# PCIE_Connector.net
KiCad netlist of a schematic drawn in Altium Designer
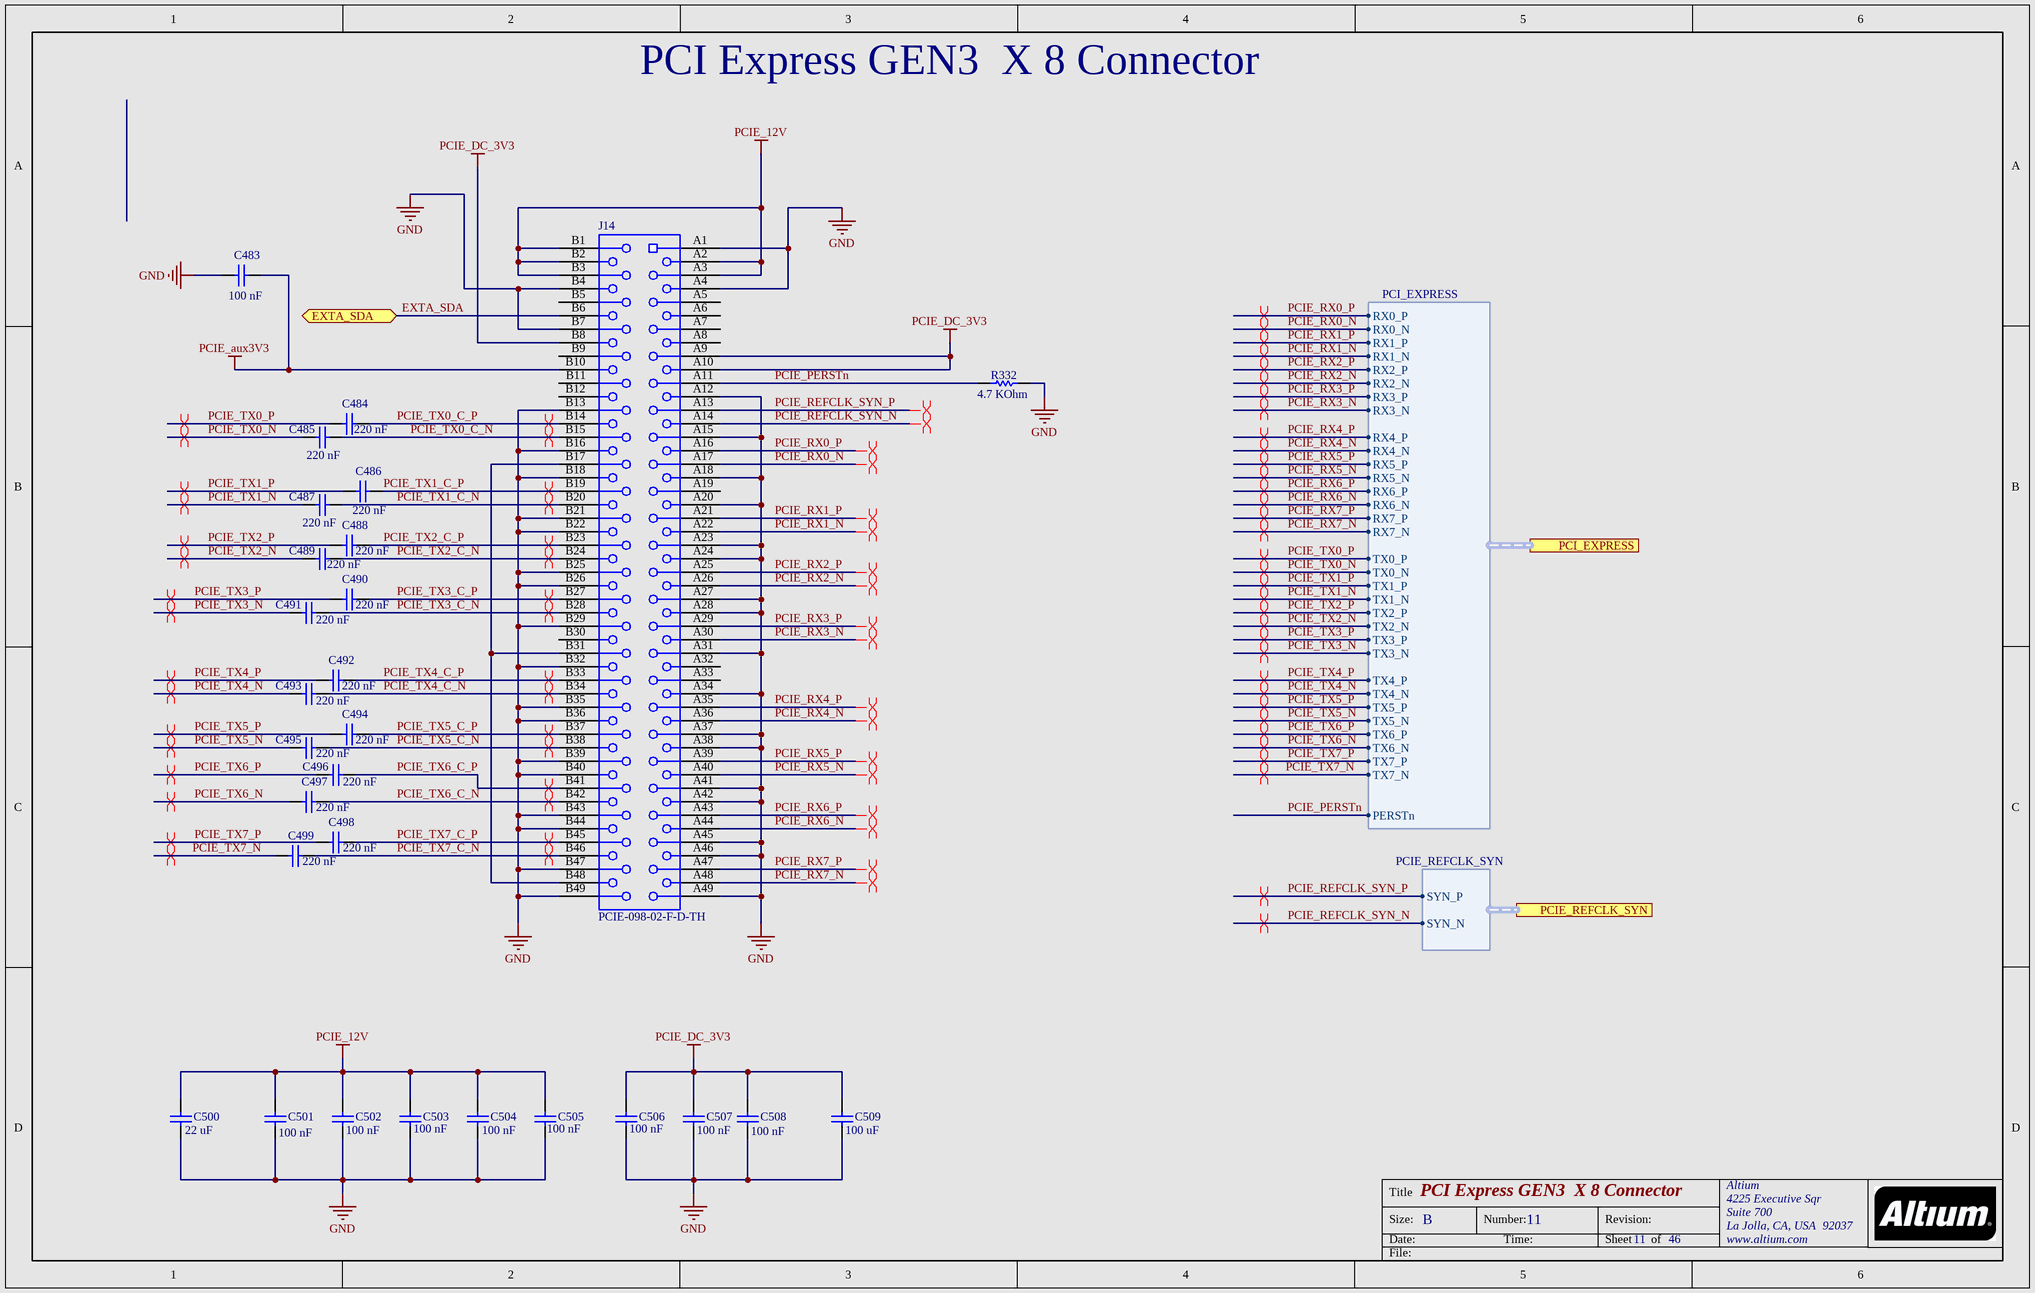
[diagram p0: PCIE_Connector.SchDoc]

(export (version "E")
  (design (tool "Eeschema 10.0.6"))
  (components
    (comp (ref "C483")
      (value "C1005X7R1E104M")
      (footprint "CAPC1005X55X10LL05")
      (description "Chip Capacitor, 0.1 uF, +/- 20%, 25 V, -55 to 125 degC, 0402 (1005 Metric), RoHS, Tape and Reel")
      (fields (field (name "TOLERANCE") "20%") (field (name "CAPACITANCE") "100 nF"))
      (libsource (lib "Altium Content Vault") (part "CAP-NP-2"))
    )
    (comp (ref "C484")
      (value "GRM155R61A224KE19D")
      (footprint "CAPC1005X55X25NL05T10")
      (description "Chip Capacitor, 220 nF, +/- 10%, 10 V, -55 to 85 degC, 0402 (1005 Metric), RoHS, Tape and Reel")
      (fields
        (field (name "TOLERANCE") "10%")
        (field (name "CAPACITANCE") "220 nF")
        (field (name "MANUFACTURER") "Basic Passives")
      )
      (libsource (lib "Altium Content Vault") (part "CAP-NP-2"))
    )
    (comp (ref "C485")
      (value "GRM155R61A224KE19D")
      (footprint "CAPC1005X55X25NL05T10")
      (description "Chip Capacitor, 220 nF, +/- 10%, 10 V, -55 to 85 degC, 0402 (1005 Metric), RoHS, Tape and Reel")
      (fields
        (field (name "TOLERANCE") "10%")
        (field (name "CAPACITANCE") "220 nF")
        (field (name "MANUFACTURER") "Basic Passives")
      )
      (libsource (lib "Altium Content Vault") (part "CAP-NP-2"))
    )
    (comp (ref "C486")
      (value "GRM155R61A224KE19D")
      (footprint "CAPC1005X55X25NL05T10")
      (description "Chip Capacitor, 220 nF, +/- 10%, 10 V, -55 to 85 degC, 0402 (1005 Metric), RoHS, Tape and Reel")
      (fields
        (field (name "TOLERANCE") "10%")
        (field (name "CAPACITANCE") "220 nF")
        (field (name "MANUFACTURER") "Basic Passives")
      )
      (libsource (lib "Altium Content Vault") (part "CAP-NP-2"))
    )
    (comp (ref "C487")
      (value "GRM155R61A224KE19D")
      (footprint "CAPC1005X55X25NL05T10")
      (description "Chip Capacitor, 220 nF, +/- 10%, 10 V, -55 to 85 degC, 0402 (1005 Metric), RoHS, Tape and Reel")
      (fields
        (field (name "TOLERANCE") "10%")
        (field (name "CAPACITANCE") "220 nF")
        (field (name "MANUFACTURER") "Basic Passives")
      )
      (libsource (lib "Altium Content Vault") (part "CAP-NP-2"))
    )
    (comp (ref "C488")
      (value "GRM155R61A224KE19D")
      (footprint "CAPC1005X55X25NL05T10")
      (description "Chip Capacitor, 220 nF, +/- 10%, 10 V, -55 to 85 degC, 0402 (1005 Metric), RoHS, Tape and Reel")
      (fields
        (field (name "TOLERANCE") "10%")
        (field (name "CAPACITANCE") "220 nF")
        (field (name "MANUFACTURER") "Basic Passives")
      )
      (libsource (lib "Altium Content Vault") (part "CAP-NP-2"))
    )
    (comp (ref "C489")
      (value "GRM155R61A224KE19D")
      (footprint "CAPC1005X55X25NL05T10")
      (description "Chip Capacitor, 220 nF, +/- 10%, 10 V, -55 to 85 degC, 0402 (1005 Metric), RoHS, Tape and Reel")
      (fields
        (field (name "TOLERANCE") "10%")
        (field (name "CAPACITANCE") "220 nF")
        (field (name "MANUFACTURER") "Basic Passives")
      )
      (libsource (lib "Altium Content Vault") (part "CAP-NP-2"))
    )
    (comp (ref "C490")
      (value "GRM155R61A224KE19D")
      (footprint "CAPC1005X55X25NL05T10")
      (description "Chip Capacitor, 220 nF, +/- 10%, 10 V, -55 to 85 degC, 0402 (1005 Metric), RoHS, Tape and Reel")
      (fields
        (field (name "TOLERANCE") "10%")
        (field (name "CAPACITANCE") "220 nF")
        (field (name "MANUFACTURER") "Basic Passives")
      )
      (libsource (lib "Altium Content Vault") (part "CAP-NP-2"))
    )
    (comp (ref "C491")
      (value "GRM155R61A224KE19D")
      (footprint "CAPC1005X55X25NL05T10")
      (description "Chip Capacitor, 220 nF, +/- 10%, 10 V, -55 to 85 degC, 0402 (1005 Metric), RoHS, Tape and Reel")
      (fields
        (field (name "TOLERANCE") "10%")
        (field (name "CAPACITANCE") "220 nF")
        (field (name "MANUFACTURER") "Basic Passives")
      )
      (libsource (lib "Altium Content Vault") (part "CAP-NP-2"))
    )
    (comp (ref "C492")
      (value "GRM155R61A224KE19D")
      (footprint "CAPC1005X55X25NL05T10")
      (description "Chip Capacitor, 220 nF, +/- 10%, 10 V, -55 to 85 degC, 0402 (1005 Metric), RoHS, Tape and Reel")
      (fields
        (field (name "TOLERANCE") "10%")
        (field (name "CAPACITANCE") "220 nF")
        (field (name "MANUFACTURER") "Basic Passives")
      )
      (libsource (lib "Altium Content Vault") (part "CAP-NP-2"))
    )
    (comp (ref "C493")
      (value "GRM155R61A224KE19D")
      (footprint "CAPC1005X55X25NL05T10")
      (description "Chip Capacitor, 220 nF, +/- 10%, 10 V, -55 to 85 degC, 0402 (1005 Metric), RoHS, Tape and Reel")
      (fields
        (field (name "TOLERANCE") "10%")
        (field (name "CAPACITANCE") "220 nF")
        (field (name "MANUFACTURER") "Basic Passives")
      )
      (libsource (lib "Altium Content Vault") (part "CAP-NP-2"))
    )
    (comp (ref "C494")
      (value "GRM155R61A224KE19D")
      (footprint "CAPC1005X55X25NL05T10")
      (description "Chip Capacitor, 220 nF, +/- 10%, 10 V, -55 to 85 degC, 0402 (1005 Metric), RoHS, Tape and Reel")
      (fields
        (field (name "TOLERANCE") "10%")
        (field (name "CAPACITANCE") "220 nF")
        (field (name "MANUFACTURER") "Basic Passives")
      )
      (libsource (lib "Altium Content Vault") (part "CAP-NP-2"))
    )
    (comp (ref "C495")
      (value "GRM155R61A224KE19D")
      (footprint "CAPC1005X55X25NL05T10")
      (description "Chip Capacitor, 220 nF, +/- 10%, 10 V, -55 to 85 degC, 0402 (1005 Metric), RoHS, Tape and Reel")
      (fields
        (field (name "TOLERANCE") "10%")
        (field (name "CAPACITANCE") "220 nF")
        (field (name "MANUFACTURER") "Basic Passives")
      )
      (libsource (lib "Altium Content Vault") (part "CAP-NP-2"))
    )
    (comp (ref "C496")
      (value "GRM155R61A224KE19D")
      (footprint "CAPC1005X55X25NL05T10")
      (description "Chip Capacitor, 220 nF, +/- 10%, 10 V, -55 to 85 degC, 0402 (1005 Metric), RoHS, Tape and Reel")
      (fields
        (field (name "TOLERANCE") "10%")
        (field (name "CAPACITANCE") "220 nF")
        (field (name "MANUFACTURER") "Basic Passives")
      )
      (libsource (lib "Altium Content Vault") (part "CAP-NP-2"))
    )
    (comp (ref "C497")
      (value "GRM155R61A224KE19D")
      (footprint "CAPC1005X55X25NL05T10")
      (description "Chip Capacitor, 220 nF, +/- 10%, 10 V, -55 to 85 degC, 0402 (1005 Metric), RoHS, Tape and Reel")
      (fields
        (field (name "TOLERANCE") "10%")
        (field (name "CAPACITANCE") "220 nF")
        (field (name "MANUFACTURER") "Basic Passives")
      )
      (libsource (lib "Altium Content Vault") (part "CAP-NP-2"))
    )
    (comp (ref "C498")
      (value "GRM155R61A224KE19D")
      (footprint "CAPC1005X55X25NL05T10")
      (description "Chip Capacitor, 220 nF, +/- 10%, 10 V, -55 to 85 degC, 0402 (1005 Metric), RoHS, Tape and Reel")
      (fields
        (field (name "TOLERANCE") "10%")
        (field (name "CAPACITANCE") "220 nF")
        (field (name "MANUFACTURER") "Basic Passives")
      )
      (libsource (lib "Altium Content Vault") (part "CAP-NP-2"))
    )
    (comp (ref "C499")
      (value "GRM155R61A224KE19D")
      (footprint "CAPC1005X55X25NL05T10")
      (description "Chip Capacitor, 220 nF, +/- 10%, 10 V, -55 to 85 degC, 0402 (1005 Metric), RoHS, Tape and Reel")
      (fields
        (field (name "TOLERANCE") "10%")
        (field (name "CAPACITANCE") "220 nF")
        (field (name "MANUFACTURER") "Basic Passives")
      )
      (libsource (lib "Altium Content Vault") (part "CAP-NP-2"))
    )
    (comp (ref "C500")
      (value "GRM31CR61E226KE15L")
      (footprint "CAPC3216X180X55ML20T25")
      (description "Chip Capacitor, 22 uF, +/- 10%, 25 V, -55 to 85 degC, 1206 (3216 Metric), RoHS, Tape and Reel")
      (fields (field (name "TOLERANCE") "10%") (field (name "CAPACITANCE") "22 uF"))
      (libsource (lib "Altium Content Vault") (part "CAP-NP-2"))
    )
    (comp (ref "C501")
      (value "C1005X7R1E104M")
      (footprint "CAPC1005X55X10LL05")
      (description "Chip Capacitor, 0.1 uF, +/- 20%, 25 V, -55 to 125 degC, 0402 (1005 Metric), RoHS, Tape and Reel")
      (fields (field (name "TOLERANCE") "20%") (field (name "CAPACITANCE") "100 nF"))
      (libsource (lib "Altium Content Vault") (part "CAP-NP-2"))
    )
    (comp (ref "C502")
      (value "C1005X7R1E104M")
      (footprint "CAPC1005X55X10LL05")
      (description "Chip Capacitor, 0.1 uF, +/- 20%, 25 V, -55 to 125 degC, 0402 (1005 Metric), RoHS, Tape and Reel")
      (fields (field (name "TOLERANCE") "20%") (field (name "CAPACITANCE") "100 nF"))
      (libsource (lib "Altium Content Vault") (part "CAP-NP-2"))
    )
    (comp (ref "C503")
      (value "C1005X7R1E104M")
      (footprint "CAPC1005X55X10LL05")
      (description "Chip Capacitor, 0.1 uF, +/- 20%, 25 V, -55 to 125 degC, 0402 (1005 Metric), RoHS, Tape and Reel")
      (fields (field (name "TOLERANCE") "20%") (field (name "CAPACITANCE") "100 nF"))
      (libsource (lib "Altium Content Vault") (part "CAP-NP-2"))
    )
    (comp (ref "C504")
      (value "C1005X7R1E104M")
      (footprint "CAPC1005X55X10LL05")
      (description "Chip Capacitor, 0.1 uF, +/- 20%, 25 V, -55 to 125 degC, 0402 (1005 Metric), RoHS, Tape and Reel")
      (fields (field (name "TOLERANCE") "20%") (field (name "CAPACITANCE") "100 nF"))
      (libsource (lib "Altium Content Vault") (part "CAP-NP-2"))
    )
    (comp (ref "C505")
      (value "C1005X7R1E104M")
      (footprint "CAPC1005X55X10LL05")
      (description "Chip Capacitor, 0.1 uF, +/- 20%, 25 V, -55 to 125 degC, 0402 (1005 Metric), RoHS, Tape and Reel")
      (fields (field (name "TOLERANCE") "20%") (field (name "CAPACITANCE") "100 nF"))
      (libsource (lib "Altium Content Vault") (part "CAP-NP-2"))
    )
    (comp (ref "C506")
      (value "C1005X7R1E104M")
      (footprint "CAPC1005X55X10LL05")
      (description "Chip Capacitor, 0.1 uF, +/- 20%, 25 V, -55 to 125 degC, 0402 (1005 Metric), RoHS, Tape and Reel")
      (fields (field (name "TOLERANCE") "20%") (field (name "CAPACITANCE") "100 nF"))
      (libsource (lib "Altium Content Vault") (part "CAP-NP-2"))
    )
    (comp (ref "C507")
      (value "C1005X7R1E104M")
      (footprint "CAPC1005X55X10LL05")
      (description "Chip Capacitor, 0.1 uF, +/- 20%, 25 V, -55 to 125 degC, 0402 (1005 Metric), RoHS, Tape and Reel")
      (fields (field (name "TOLERANCE") "20%") (field (name "CAPACITANCE") "100 nF"))
      (libsource (lib "Altium Content Vault") (part "CAP-NP-2"))
    )
    (comp (ref "C508")
      (value "C1005X7R1E104M")
      (footprint "CAPC1005X55X10LL05")
      (description "Chip Capacitor, 0.1 uF, +/- 20%, 25 V, -55 to 125 degC, 0402 (1005 Metric), RoHS, Tape and Reel")
      (fields (field (name "TOLERANCE") "20%") (field (name "CAPACITANCE") "100 nF"))
      (libsource (lib "Altium Content Vault") (part "CAP-NP-2"))
    )
    (comp (ref "C509")
      (value "GRM31CR60J107ME39L")
      (footprint "CAPC3216X190X55ML30T25")
      (description "Chip Capacitor, 100 uF, +/- 20%, 6.3 V, -55 to 85 degC, 1206 (3216 Metric), RoHS, Tape and Reel")
      (fields (field (name "TOLERANCE") "20%") (field (name "CAPACITANCE") "100 uF"))
      (libsource (lib "Altium Content Vault") (part "CAP-NP-2"))
    )
    (comp (ref "J14")
      (value "PCIE-098-02-F-D-TH")
      (footprint "SMTC-PCIE-098-02-F-D-TH_V")
      (fields (field (name "MANUFACTURER") "Samtec"))
      (libsource (lib "Altium Content Vault") (part "CMP-1707-00002-1"))
    )
    (comp (ref "R332")
      (value "ERJ-2RKF4701X")
      (footprint "RESC1005X40X25LL05T05")
      (description "Chip Resistor, 4.7 KOhm, +/- 1%, 0.1 W, -55 to 155 degC, 0402 (1005 Metric), RoHS, Tape and Reel")
      (fields (field (name "TOLERANCE") "1%") (field (name "RESISTANCE") "4.7 KOhm"))
      (libsource (lib "Altium Content Vault") (part "RES-2"))
    )
  )
  (nets
    (net (code "3") (name "/EXTA_SDA") (class "Default")
      (node (ref "J14") (pin "B6") (pinfunction "B6_B6") (pintype "passive"))
    )
    (net (code "4") (name "/PCIE_PERSTn") (class "Default")
      (node (ref "J14") (pin "A11") (pinfunction "A11_A11") (pintype "passive"))
      (node (ref "R332") (pin "1") (pinfunction "1_1") (pintype "passive"))
    )
    (net (code "5") (name "/PCIE_REFCLK_SYN_N") (class "Default")
      (node (ref "J14") (pin "A14") (pinfunction "A14_A14") (pintype "passive"))
    )
    (net (code "6") (name "/PCIE_REFCLK_SYN_P") (class "Default")
      (node (ref "J14") (pin "A13") (pinfunction "A13_A13") (pintype "passive"))
    )
    (net (code "7") (name "/PCIE_RX0_N") (class "Default")
      (node (ref "J14") (pin "A17") (pinfunction "A17_A17") (pintype "passive"))
    )
    (net (code "8") (name "/PCIE_RX0_P") (class "Default")
      (node (ref "J14") (pin "A16") (pinfunction "A16_A16") (pintype "passive"))
    )
    (net (code "9") (name "/PCIE_RX1_N") (class "Default")
      (node (ref "J14") (pin "A22") (pinfunction "A22_A22") (pintype "passive"))
    )
    (net (code "10") (name "/PCIE_RX1_P") (class "Default")
      (node (ref "J14") (pin "A21") (pinfunction "A21_A21") (pintype "passive"))
    )
    (net (code "11") (name "/PCIE_RX2_N") (class "Default")
      (node (ref "J14") (pin "A26") (pinfunction "A26_A26") (pintype "passive"))
    )
    (net (code "12") (name "/PCIE_RX2_P") (class "Default")
      (node (ref "J14") (pin "A25") (pinfunction "A25_A25") (pintype "passive"))
    )
    (net (code "13") (name "/PCIE_RX3_N") (class "Default")
      (node (ref "J14") (pin "A30") (pinfunction "A30_A30") (pintype "passive"))
    )
    (net (code "14") (name "/PCIE_RX3_P") (class "Default")
      (node (ref "J14") (pin "A29") (pinfunction "A29_A29") (pintype "passive"))
    )
    (net (code "15") (name "/PCIE_RX4_N") (class "Default")
      (node (ref "J14") (pin "A36") (pinfunction "A36_A36") (pintype "passive"))
    )
    (net (code "16") (name "/PCIE_RX4_P") (class "Default")
      (node (ref "J14") (pin "A35") (pinfunction "A35_A35") (pintype "passive"))
    )
    (net (code "17") (name "/PCIE_RX5_N") (class "Default")
      (node (ref "J14") (pin "A40") (pinfunction "A40_A40") (pintype "passive"))
    )
    (net (code "18") (name "/PCIE_RX5_P") (class "Default")
      (node (ref "J14") (pin "A39") (pinfunction "A39_A39") (pintype "passive"))
    )
    (net (code "19") (name "/PCIE_RX6_N") (class "Default")
      (node (ref "J14") (pin "A44") (pinfunction "A44_A44") (pintype "passive"))
    )
    (net (code "20") (name "/PCIE_RX6_P") (class "Default")
      (node (ref "J14") (pin "A43") (pinfunction "A43_A43") (pintype "passive"))
    )
    (net (code "21") (name "/PCIE_RX7_N") (class "Default")
      (node (ref "J14") (pin "A48") (pinfunction "A48_A48") (pintype "passive"))
    )
    (net (code "22") (name "/PCIE_RX7_P") (class "Default")
      (node (ref "J14") (pin "A47") (pinfunction "A47_A47") (pintype "passive"))
    )
    (net (code "23") (name "/PCIE_TX0_C_N") (class "Default")
      (node (ref "C485") (pin "2") (pinfunction "2_2") (pintype "passive"))
      (node (ref "J14") (pin "B15") (pinfunction "B15_B15") (pintype "passive"))
    )
    (net (code "24") (name "/PCIE_TX0_C_P") (class "Default")
      (node (ref "C484") (pin "2") (pinfunction "2_2") (pintype "passive"))
      (node (ref "J14") (pin "B14") (pinfunction "B14_B14") (pintype "passive"))
    )
    (net (code "25") (name "/PCIE_TX0_N") (class "Default")
      (node (ref "C485") (pin "1") (pinfunction "1_1") (pintype "passive"))
    )
    (net (code "26") (name "/PCIE_TX0_P") (class "Default")
      (node (ref "C484") (pin "1") (pinfunction "1_1") (pintype "passive"))
    )
    (net (code "27") (name "/PCIE_TX1_C_N") (class "Default")
      (node (ref "C487") (pin "2") (pinfunction "2_2") (pintype "passive"))
      (node (ref "J14") (pin "B20") (pinfunction "B20_B20") (pintype "passive"))
    )
    (net (code "28") (name "/PCIE_TX1_C_P") (class "Default")
      (node (ref "C486") (pin "2") (pinfunction "2_2") (pintype "passive"))
      (node (ref "J14") (pin "B19") (pinfunction "B19_B19") (pintype "passive"))
    )
    (net (code "29") (name "/PCIE_TX1_N") (class "Default")
      (node (ref "C487") (pin "1") (pinfunction "1_1") (pintype "passive"))
    )
    (net (code "30") (name "/PCIE_TX1_P") (class "Default")
      (node (ref "C486") (pin "1") (pinfunction "1_1") (pintype "passive"))
    )
    (net (code "31") (name "/PCIE_TX2_C_N") (class "Default")
      (node (ref "C489") (pin "2") (pinfunction "2_2") (pintype "passive"))
      (node (ref "J14") (pin "B24") (pinfunction "B24_B24") (pintype "passive"))
    )
    (net (code "32") (name "/PCIE_TX2_C_P") (class "Default")
      (node (ref "C488") (pin "2") (pinfunction "2_2") (pintype "passive"))
      (node (ref "J14") (pin "B23") (pinfunction "B23_B23") (pintype "passive"))
    )
    (net (code "33") (name "/PCIE_TX2_N") (class "Default")
      (node (ref "C489") (pin "1") (pinfunction "1_1") (pintype "passive"))
    )
    (net (code "34") (name "/PCIE_TX2_P") (class "Default")
      (node (ref "C488") (pin "1") (pinfunction "1_1") (pintype "passive"))
    )
    (net (code "35") (name "/PCIE_TX3_C_N") (class "Default")
      (node (ref "C491") (pin "2") (pinfunction "2_2") (pintype "passive"))
      (node (ref "J14") (pin "B28") (pinfunction "B28_B28") (pintype "passive"))
    )
    (net (code "36") (name "/PCIE_TX3_C_P") (class "Default")
      (node (ref "C490") (pin "2") (pinfunction "2_2") (pintype "passive"))
      (node (ref "J14") (pin "B27") (pinfunction "B27_B27") (pintype "passive"))
    )
    (net (code "37") (name "/PCIE_TX3_N") (class "Default")
      (node (ref "C491") (pin "1") (pinfunction "1_1") (pintype "passive"))
    )
    (net (code "38") (name "/PCIE_TX3_P") (class "Default")
      (node (ref "C490") (pin "1") (pinfunction "1_1") (pintype "passive"))
    )
    (net (code "39") (name "/PCIE_TX4_C_N") (class "Default")
      (node (ref "C493") (pin "2") (pinfunction "2_2") (pintype "passive"))
      (node (ref "J14") (pin "B34") (pinfunction "B34_B34") (pintype "passive"))
    )
    (net (code "40") (name "/PCIE_TX4_C_P") (class "Default")
      (node (ref "C492") (pin "2") (pinfunction "2_2") (pintype "passive"))
      (node (ref "J14") (pin "B33") (pinfunction "B33_B33") (pintype "passive"))
    )
    (net (code "41") (name "/PCIE_TX4_N") (class "Default")
      (node (ref "C493") (pin "1") (pinfunction "1_1") (pintype "passive"))
    )
    (net (code "42") (name "/PCIE_TX4_P") (class "Default")
      (node (ref "C492") (pin "1") (pinfunction "1_1") (pintype "passive"))
    )
    (net (code "43") (name "/PCIE_TX5_C_N") (class "Default")
      (node (ref "C495") (pin "2") (pinfunction "2_2") (pintype "passive"))
      (node (ref "J14") (pin "B38") (pinfunction "B38_B38") (pintype "passive"))
    )
    (net (code "44") (name "/PCIE_TX5_C_P") (class "Default")
      (node (ref "C494") (pin "2") (pinfunction "2_2") (pintype "passive"))
      (node (ref "J14") (pin "B37") (pinfunction "B37_B37") (pintype "passive"))
    )
    (net (code "45") (name "/PCIE_TX5_N") (class "Default")
      (node (ref "C495") (pin "1") (pinfunction "1_1") (pintype "passive"))
    )
    (net (code "46") (name "/PCIE_TX5_P") (class "Default")
      (node (ref "C494") (pin "1") (pinfunction "1_1") (pintype "passive"))
    )
    (net (code "47") (name "/PCIE_TX6_C_N") (class "Default")
      (node (ref "C497") (pin "2") (pinfunction "2_2") (pintype "passive"))
      (node (ref "J14") (pin "B42") (pinfunction "B42_B42") (pintype "passive"))
    )
    (net (code "48") (name "/PCIE_TX6_C_P") (class "Default")
      (node (ref "C496") (pin "2") (pinfunction "2_2") (pintype "passive"))
      (node (ref "J14") (pin "B41") (pinfunction "B41_B41") (pintype "passive"))
    )
    (net (code "49") (name "/PCIE_TX6_N") (class "Default")
      (node (ref "C497") (pin "1") (pinfunction "1_1") (pintype "passive"))
    )
    (net (code "50") (name "/PCIE_TX6_P") (class "Default")
      (node (ref "C496") (pin "1") (pinfunction "1_1") (pintype "passive"))
    )
    (net (code "51") (name "/PCIE_TX7_C_N") (class "Default")
      (node (ref "C499") (pin "2") (pinfunction "2_2") (pintype "passive"))
      (node (ref "J14") (pin "B46") (pinfunction "B46_B46") (pintype "passive"))
    )
    (net (code "52") (name "/PCIE_TX7_C_P") (class "Default")
      (node (ref "C498") (pin "2") (pinfunction "2_2") (pintype "passive"))
      (node (ref "J14") (pin "B45") (pinfunction "B45_B45") (pintype "passive"))
    )
    (net (code "53") (name "/PCIE_TX7_N") (class "Default")
      (node (ref "C499") (pin "1") (pinfunction "1_1") (pintype "passive"))
    )
    (net (code "54") (name "/PCIE_TX7_P") (class "Default")
      (node (ref "C498") (pin "1") (pinfunction "1_1") (pintype "passive"))
    )
    (net (code "57") (name "GND") (class "Default")
      (node (ref "C483") (pin "1") (pinfunction "1_1") (pintype "passive"))
      (node (ref "C500") (pin "1") (pinfunction "1_1") (pintype "passive"))
      (node (ref "C501") (pin "1") (pinfunction "1_1") (pintype "passive"))
      (node (ref "C502") (pin "1") (pinfunction "1_1") (pintype "passive"))
      (node (ref "C503") (pin "1") (pinfunction "1_1") (pintype "passive"))
      (node (ref "C504") (pin "1") (pinfunction "1_1") (pintype "passive"))
      (node (ref "C505") (pin "1") (pinfunction "1_1") (pintype "passive"))
      (node (ref "C506") (pin "1") (pinfunction "1_1") (pintype "passive"))
      (node (ref "C507") (pin "1") (pinfunction "1_1") (pintype "passive"))
      (node (ref "C508") (pin "1") (pinfunction "1_1") (pintype "passive"))
      (node (ref "C509") (pin "1") (pinfunction "1_1") (pintype "passive"))
      (node (ref "J14") (pin "A1") (pinfunction "A1_A1") (pintype "passive"))
      (node (ref "J14") (pin "A12") (pinfunction "A12_A12") (pintype "passive"))
      (node (ref "J14") (pin "A15") (pinfunction "A15_A15") (pintype "passive"))
      (node (ref "J14") (pin "A18") (pinfunction "A18_A18") (pintype "passive"))
      (node (ref "J14") (pin "A20") (pinfunction "A20_A20") (pintype "passive"))
      (node (ref "J14") (pin "A23") (pinfunction "A23_A23") (pintype "passive"))
      (node (ref "J14") (pin "A24") (pinfunction "A24_A24") (pintype "passive"))
      (node (ref "J14") (pin "A27") (pinfunction "A27_A27") (pintype "passive"))
      (node (ref "J14") (pin "A28") (pinfunction "A28_A28") (pintype "passive"))
      (node (ref "J14") (pin "A31") (pinfunction "A31_A31") (pintype "passive"))
      (node (ref "J14") (pin "A34") (pinfunction "A34_A34") (pintype "passive"))
      (node (ref "J14") (pin "A37") (pinfunction "A37_A37") (pintype "passive"))
      (node (ref "J14") (pin "A38") (pinfunction "A38_A38") (pintype "passive"))
      (node (ref "J14") (pin "A4") (pinfunction "A4_A4") (pintype "passive"))
      (node (ref "J14") (pin "A41") (pinfunction "A41_A41") (pintype "passive"))
      (node (ref "J14") (pin "A42") (pinfunction "A42_A42") (pintype "passive"))
      (node (ref "J14") (pin "A45") (pinfunction "A45_A45") (pintype "passive"))
      (node (ref "J14") (pin "A46") (pinfunction "A46_A46") (pintype "passive"))
      (node (ref "J14") (pin "A49") (pinfunction "A49_A49") (pintype "passive"))
      (node (ref "J14") (pin "B13") (pinfunction "B13_B13") (pintype "passive"))
      (node (ref "J14") (pin "B16") (pinfunction "B16_B16") (pintype "passive"))
      (node (ref "J14") (pin "B18") (pinfunction "B18_B18") (pintype "passive"))
      (node (ref "J14") (pin "B21") (pinfunction "B21_B21") (pintype "passive"))
      (node (ref "J14") (pin "B22") (pinfunction "B22_B22") (pintype "passive"))
      (node (ref "J14") (pin "B25") (pinfunction "B25_B25") (pintype "passive"))
      (node (ref "J14") (pin "B26") (pinfunction "B26_B26") (pintype "passive"))
      (node (ref "J14") (pin "B29") (pinfunction "B29_B29") (pintype "passive"))
      (node (ref "J14") (pin "B32") (pinfunction "B32_B32") (pintype "passive"))
      (node (ref "J14") (pin "B35") (pinfunction "B35_B35") (pintype "passive"))
      (node (ref "J14") (pin "B36") (pinfunction "B36_B36") (pintype "passive"))
      (node (ref "J14") (pin "B39") (pinfunction "B39_B39") (pintype "passive"))
      (node (ref "J14") (pin "B4") (pinfunction "B4_B4") (pintype "passive"))
      (node (ref "J14") (pin "B40") (pinfunction "B40_B40") (pintype "passive"))
      (node (ref "J14") (pin "B43") (pinfunction "B43_B43") (pintype "passive"))
      (node (ref "J14") (pin "B44") (pinfunction "B44_B44") (pintype "passive"))
      (node (ref "J14") (pin "B47") (pinfunction "B47_B47") (pintype "passive"))
      (node (ref "J14") (pin "B49") (pinfunction "B49_B49") (pintype "passive"))
      (node (ref "J14") (pin "B7") (pinfunction "B7_B7") (pintype "passive"))
      (node (ref "R332") (pin "2") (pinfunction "2_2") (pintype "passive"))
    )
    (net (code "58") (name "Net-(J14-PadB17)") (class "Default")
      (node (ref "J14") (pin "B17") (pinfunction "B17_B17") (pintype "passive"))
      (node (ref "J14") (pin "B31") (pinfunction "B31_B31") (pintype "passive"))
      (node (ref "J14") (pin "B48") (pinfunction "B48_B48") (pintype "passive"))
    )
    (net (code "59") (name "PCIE_12V") (class "Default")
      (node (ref "C500") (pin "2") (pinfunction "2_2") (pintype "passive"))
      (node (ref "C501") (pin "2") (pinfunction "2_2") (pintype "passive"))
      (node (ref "C502") (pin "2") (pinfunction "2_2") (pintype "passive"))
      (node (ref "C503") (pin "2") (pinfunction "2_2") (pintype "passive"))
      (node (ref "C504") (pin "2") (pinfunction "2_2") (pintype "passive"))
      (node (ref "C505") (pin "2") (pinfunction "2_2") (pintype "passive"))
      (node (ref "J14") (pin "A2") (pinfunction "A2_A2") (pintype "passive"))
      (node (ref "J14") (pin "A3") (pinfunction "A3_A3") (pintype "passive"))
      (node (ref "J14") (pin "B1") (pinfunction "B1_B1") (pintype "passive"))
      (node (ref "J14") (pin "B2") (pinfunction "B2_B2") (pintype "passive"))
      (node (ref "J14") (pin "B3") (pinfunction "B3_B3") (pintype "passive"))
    )
    (net (code "60") (name "PCIE_DC_3V3") (class "Default")
      (node (ref "C506") (pin "2") (pinfunction "2_2") (pintype "passive"))
      (node (ref "C507") (pin "2") (pinfunction "2_2") (pintype "passive"))
      (node (ref "C508") (pin "2") (pinfunction "2_2") (pintype "passive"))
      (node (ref "C509") (pin "2") (pinfunction "2_2") (pintype "passive"))
      (node (ref "J14") (pin "A10") (pinfunction "A10_A10") (pintype "passive"))
      (node (ref "J14") (pin "A9") (pinfunction "A9_A9") (pintype "passive"))
      (node (ref "J14") (pin "B8") (pinfunction "B8_B8") (pintype "passive"))
    )
    (net (code "61") (name "PCIE_aux3V3") (class "Default")
      (node (ref "C483") (pin "2") (pinfunction "2_2") (pintype "passive"))
      (node (ref "J14") (pin "B10") (pinfunction "B10_B10") (pintype "passive"))
    )
    (net (code "62") (name "unconnected-(J14-PadA5)") (class "Default")
      (node (ref "J14") (pin "A5") (pinfunction "A5_A5") (pintype "passive"))
    )
    (net (code "63") (name "unconnected-(J14-PadA6)") (class "Default")
      (node (ref "J14") (pin "A6") (pinfunction "A6_A6") (pintype "passive"))
    )
    (net (code "64") (name "unconnected-(J14-PadA7)") (class "Default")
      (node (ref "J14") (pin "A7") (pinfunction "A7_A7") (pintype "passive"))
    )
    (net (code "65") (name "unconnected-(J14-PadA8)") (class "Default")
      (node (ref "J14") (pin "A8") (pinfunction "A8_A8") (pintype "passive"))
    )
    (net (code "66") (name "unconnected-(J14-PadA19)") (class "Default")
      (node (ref "J14") (pin "A19") (pinfunction "A19_A19") (pintype "passive"))
    )
    (net (code "67") (name "unconnected-(J14-PadA32)") (class "Default")
      (node (ref "J14") (pin "A32") (pinfunction "A32_A32") (pintype "passive"))
    )
    (net (code "68") (name "unconnected-(J14-PadA33)") (class "Default")
      (node (ref "J14") (pin "A33") (pinfunction "A33_A33") (pintype "passive"))
    )
    (net (code "69") (name "unconnected-(J14-PadB5)") (class "Default")
      (node (ref "J14") (pin "B5") (pinfunction "B5_B5") (pintype "passive"))
    )
    (net (code "70") (name "unconnected-(J14-PadB9)") (class "Default")
      (node (ref "J14") (pin "B9") (pinfunction "B9_B9") (pintype "passive"))
    )
    (net (code "71") (name "unconnected-(J14-PadB11)") (class "Default")
      (node (ref "J14") (pin "B11") (pinfunction "B11_B11") (pintype "passive"))
    )
    (net (code "72") (name "unconnected-(J14-PadB12)") (class "Default")
      (node (ref "J14") (pin "B12") (pinfunction "B12_B12") (pintype "passive"))
    )
    (net (code "73") (name "unconnected-(J14-PadB30)") (class "Default")
      (node (ref "J14") (pin "B30") (pinfunction "B30_B30") (pintype "passive"))
    )
  )
)
